# mr_radar_ferret.net
KiCad netlist of a schematic drawn in EAGLE
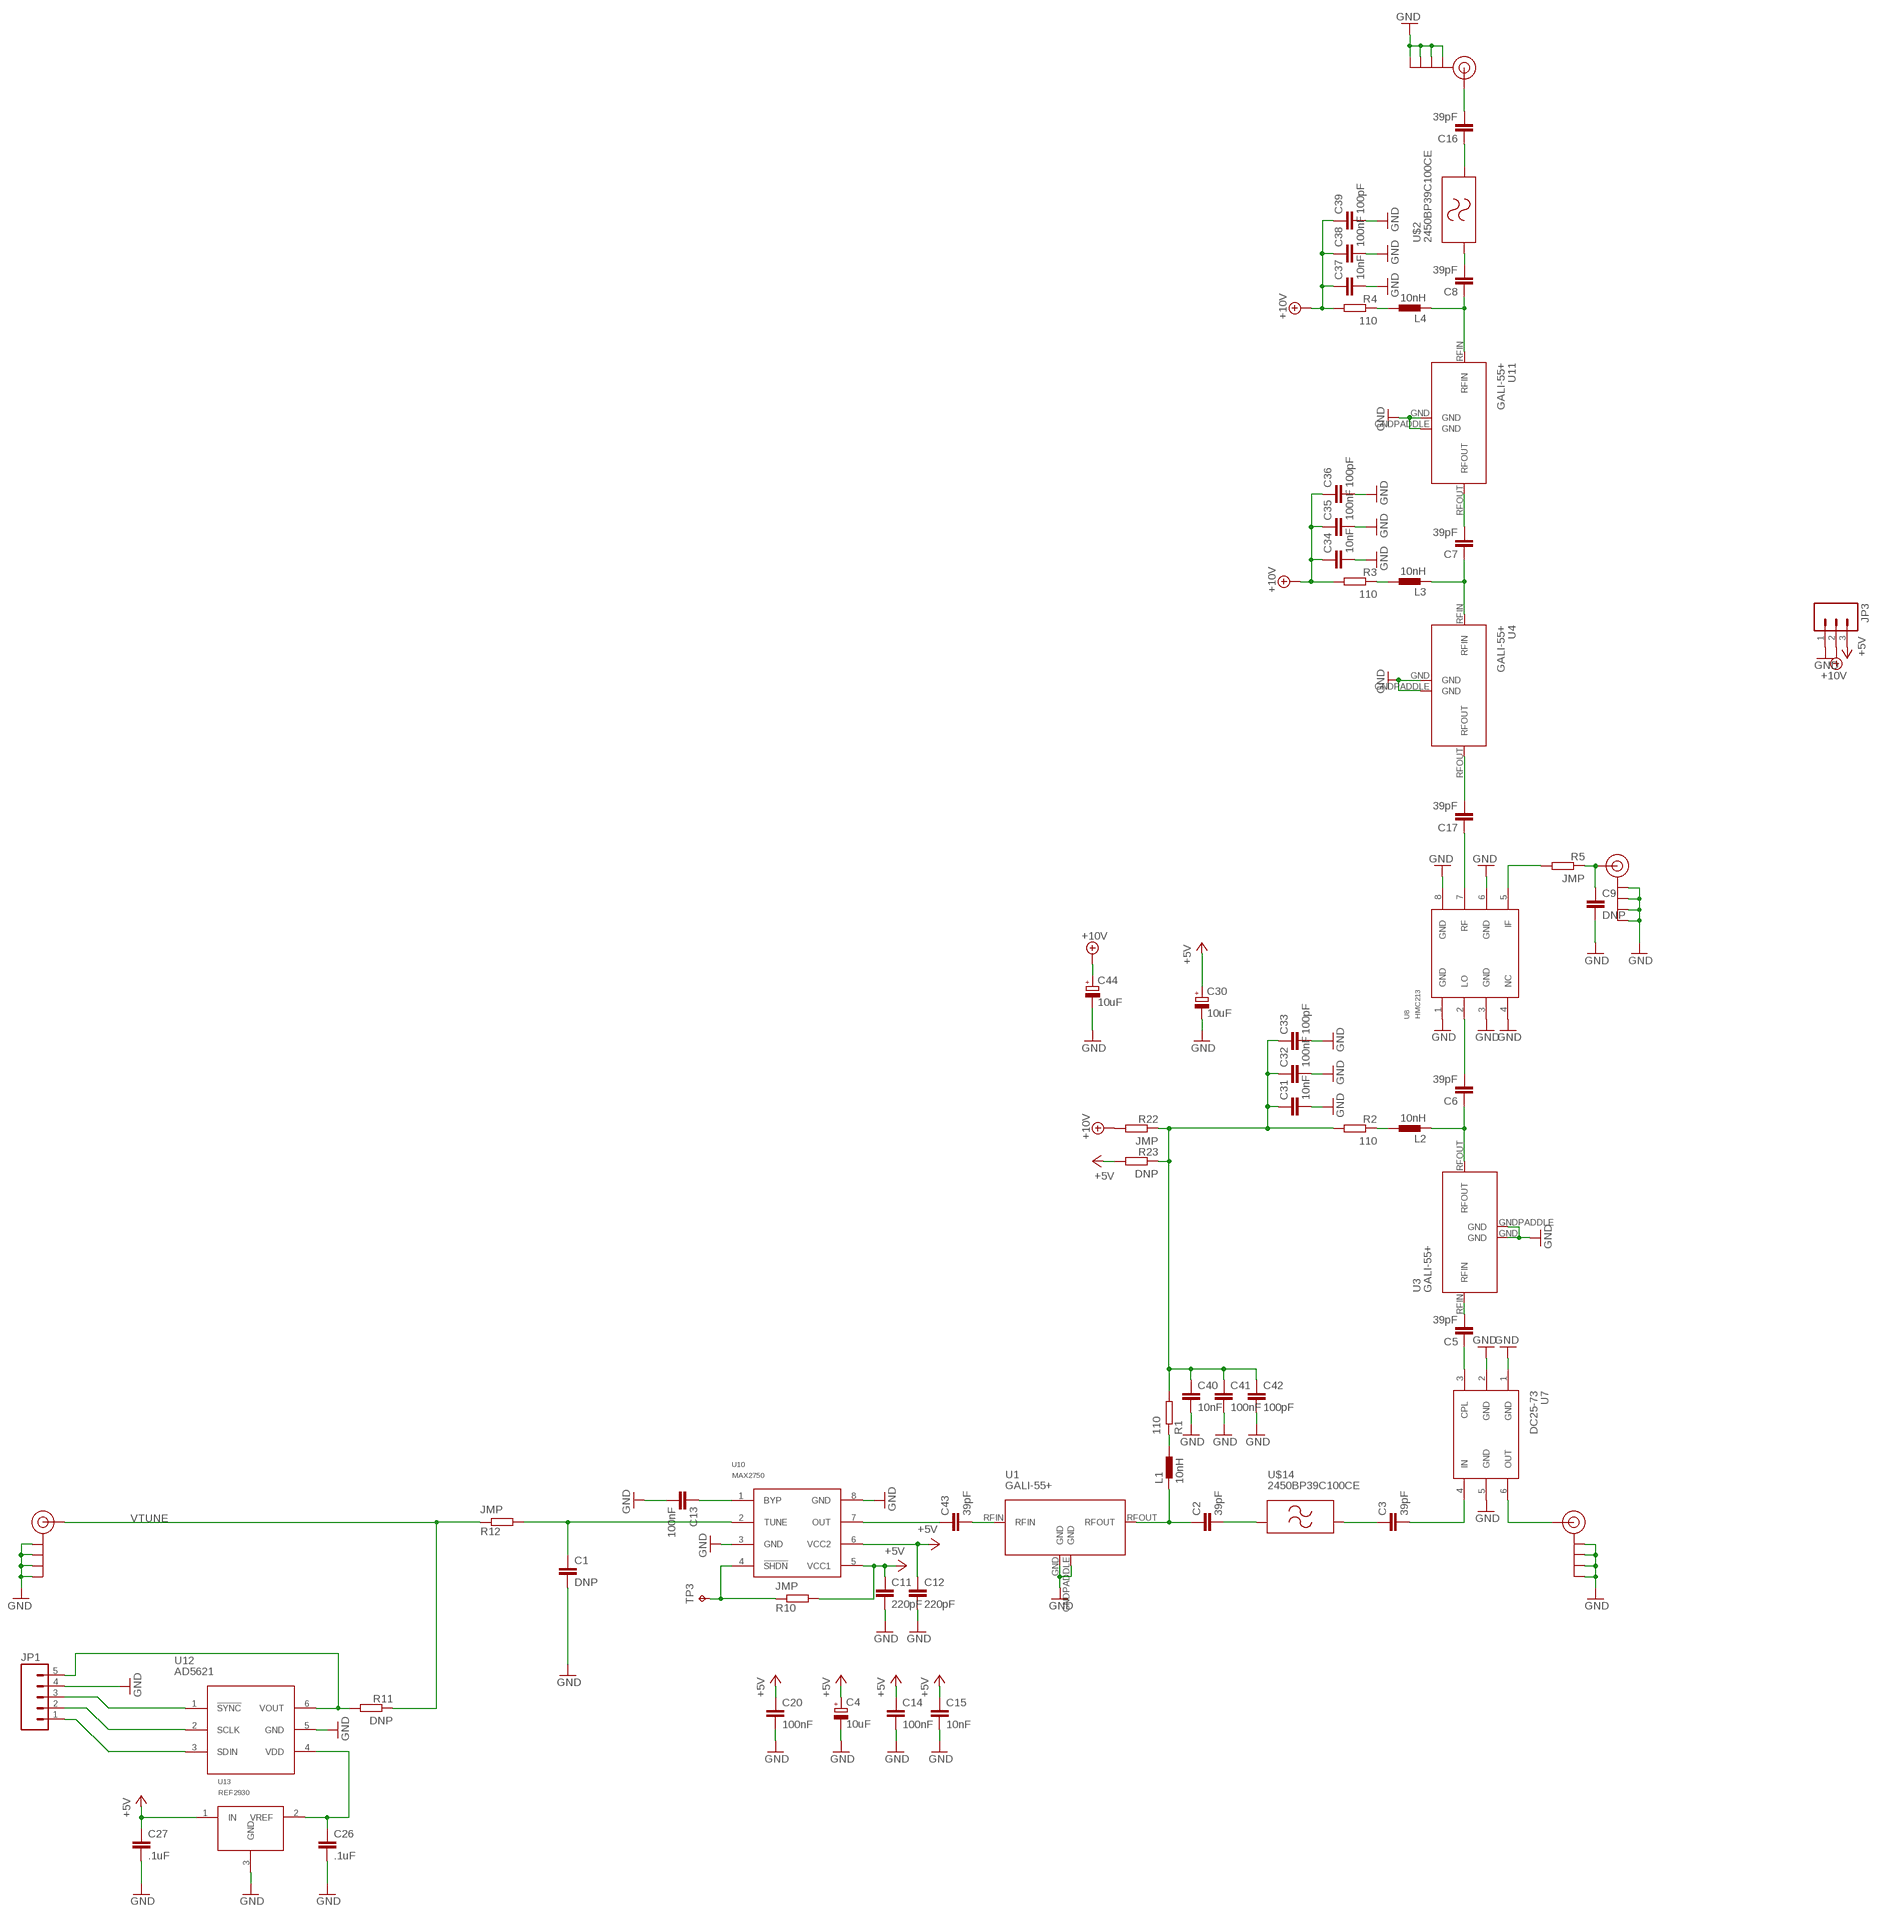
[diagram p0: schematic, sheet 1]

(export (version "E")
  (design (tool "Eeschema 10.0.6"))
  (components
    (comp (ref "C1")
      (value "DNP")
      (footprint "eagle-import:0603-CAP")
      (libsource (lib "eagle-import") (part "CAPACITOR-0603"))
    )
    (comp (ref "C2")
      (value "39pF")
      (footprint "eagle-import:0603-CAP")
      (libsource (lib "eagle-import") (part "CAPACITOR-0603"))
    )
    (comp (ref "C3")
      (value "39pF")
      (footprint "eagle-import:0603-CAP")
      (libsource (lib "eagle-import") (part "CAPACITOR-0603"))
    )
    (comp (ref "C4")
      (value "10uF")
      (footprint "eagle-import:3216_A")
      (libsource (lib "eagle-import") (part "CAPACITOR-POLA"))
    )
    (comp (ref "C5")
      (value "39pF")
      (footprint "eagle-import:0603-CAP")
      (libsource (lib "eagle-import") (part "CAPACITOR-0603"))
    )
    (comp (ref "C6")
      (value "39pF")
      (footprint "eagle-import:0603-CAP")
      (libsource (lib "eagle-import") (part "CAPACITOR-0603"))
    )
    (comp (ref "C7")
      (value "39pF")
      (footprint "eagle-import:0603-CAP")
      (libsource (lib "eagle-import") (part "CAPACITOR-0603"))
    )
    (comp (ref "C8")
      (value "39pF")
      (footprint "eagle-import:0603-CAP")
      (libsource (lib "eagle-import") (part "CAPACITOR-0603"))
    )
    (comp (ref "C9")
      (value "DNP")
      (footprint "eagle-import:0603-CAP")
      (libsource (lib "eagle-import") (part "CAPACITOR-0603"))
    )
    (comp (ref "C11")
      (value "220pF")
      (footprint "eagle-import:0603-CAP")
      (libsource (lib "eagle-import") (part "CAPACITOR-0603"))
    )
    (comp (ref "C12")
      (value "220pF")
      (footprint "eagle-import:0603-CAP")
      (libsource (lib "eagle-import") (part "CAPACITOR-0603"))
    )
    (comp (ref "C13")
      (value "100nF")
      (footprint "eagle-import:0603-CAP")
      (libsource (lib "eagle-import") (part "CAPACITOR-0603"))
    )
    (comp (ref "C14")
      (value "100nF")
      (footprint "eagle-import:0603-CAP")
      (libsource (lib "eagle-import") (part "CAPACITOR-0603"))
    )
    (comp (ref "C15")
      (value "10nF")
      (footprint "eagle-import:0603-CAP")
      (libsource (lib "eagle-import") (part "CAPACITOR-0603"))
    )
    (comp (ref "C16")
      (value "39pF")
      (footprint "eagle-import:0603-CAP")
      (libsource (lib "eagle-import") (part "CAPACITOR-0603"))
    )
    (comp (ref "C17")
      (value "39pF")
      (footprint "eagle-import:0603-CAP")
      (libsource (lib "eagle-import") (part "CAPACITOR-0603"))
    )
    (comp (ref "C20")
      (value "100nF")
      (footprint "eagle-import:0603-CAP")
      (libsource (lib "eagle-import") (part "CAPACITOR-0603"))
    )
    (comp (ref "C26")
      (value ".1uF")
      (footprint "eagle-import:0603-CAP")
      (libsource (lib "eagle-import") (part "CAPACITOR-0603"))
    )
    (comp (ref "C27")
      (value ".1uF")
      (footprint "eagle-import:0603-CAP")
      (libsource (lib "eagle-import") (part "CAPACITOR-0603"))
    )
    (comp (ref "C30")
      (value "10uF")
      (footprint "eagle-import:3216_A")
      (libsource (lib "eagle-import") (part "CAPACITOR-POLA"))
    )
    (comp (ref "C31")
      (value "10nF")
      (footprint "eagle-import:0603-CAP")
      (libsource (lib "eagle-import") (part "CAPACITOR-0603"))
    )
    (comp (ref "C32")
      (value "100nF")
      (footprint "eagle-import:0603-CAP")
      (libsource (lib "eagle-import") (part "CAPACITOR-0603"))
    )
    (comp (ref "C33")
      (value "100pF")
      (footprint "eagle-import:0603-CAP")
      (libsource (lib "eagle-import") (part "CAPACITOR-0603"))
    )
    (comp (ref "C34")
      (value "10nF")
      (footprint "eagle-import:0603-CAP")
      (libsource (lib "eagle-import") (part "CAPACITOR-0603"))
    )
    (comp (ref "C35")
      (value "100nF")
      (footprint "eagle-import:0603-CAP")
      (libsource (lib "eagle-import") (part "CAPACITOR-0603"))
    )
    (comp (ref "C36")
      (value "100pF")
      (footprint "eagle-import:0603-CAP")
      (libsource (lib "eagle-import") (part "CAPACITOR-0603"))
    )
    (comp (ref "C37")
      (value "10nF")
      (footprint "eagle-import:0603-CAP")
      (libsource (lib "eagle-import") (part "CAPACITOR-0603"))
    )
    (comp (ref "C38")
      (value "100nF")
      (footprint "eagle-import:0603-CAP")
      (libsource (lib "eagle-import") (part "CAPACITOR-0603"))
    )
    (comp (ref "C39")
      (value "100pF")
      (footprint "eagle-import:0603-CAP")
      (libsource (lib "eagle-import") (part "CAPACITOR-0603"))
    )
    (comp (ref "C40")
      (value "10nF")
      (footprint "eagle-import:0603-CAP")
      (libsource (lib "eagle-import") (part "CAPACITOR-0603"))
    )
    (comp (ref "C41")
      (value "100nF")
      (footprint "eagle-import:0603-CAP")
      (libsource (lib "eagle-import") (part "CAPACITOR-0603"))
    )
    (comp (ref "C42")
      (value "100pF")
      (footprint "eagle-import:0603-CAP")
      (libsource (lib "eagle-import") (part "CAPACITOR-0603"))
    )
    (comp (ref "C43")
      (value "39pF")
      (footprint "eagle-import:0603-CAP")
      (libsource (lib "eagle-import") (part "CAPACITOR-0603"))
    )
    (comp (ref "C44")
      (value "10uF")
      (footprint "eagle-import:3216_A")
      (libsource (lib "eagle-import") (part "CAPACITOR-POLA"))
    )
    (comp (ref "J$1")
      (value "SMA_EDGE")
      (footprint "eagle-import:SMA-EDGE")
      (libsource (lib "eagle-import") (part "SMA_EDGE"))
    )
    (comp (ref "J$2")
      (value "SMA_EDGE")
      (footprint "eagle-import:SMA-EDGE")
      (libsource (lib "eagle-import") (part "SMA_EDGE"))
    )
    (comp (ref "J$4")
      (value "SMA_EDGE")
      (footprint "eagle-import:SMA-EDGE")
      (libsource (lib "eagle-import") (part "SMA_EDGE"))
    )
    (comp (ref "J$5")
      (value "SMA_EDGE")
      (footprint "eagle-import:SMA-EDGE")
      (libsource (lib "eagle-import") (part "SMA_EDGE"))
    )
    (comp (ref "JP1")
      (value "M05PTH")
      (footprint "eagle-import:1X05")
      (libsource (lib "eagle-import") (part "M05PTH"))
    )
    (comp (ref "JP3")
      (value "M03SCREW")
      (footprint "eagle-import:SCREWTERMINAL-3.5MM-3")
      (libsource (lib "eagle-import") (part "M03SCREW"))
    )
    (comp (ref "L1")
      (value "10nH")
      (footprint "eagle-import:0603-IND")
      (libsource (lib "eagle-import") (part "INDUCTOR-0603"))
    )
    (comp (ref "L2")
      (value "10nH")
      (footprint "eagle-import:0603-IND")
      (libsource (lib "eagle-import") (part "INDUCTOR-0603"))
    )
    (comp (ref "L3")
      (value "10nH")
      (footprint "eagle-import:0603-IND")
      (libsource (lib "eagle-import") (part "INDUCTOR-0603"))
    )
    (comp (ref "L4")
      (value "10nH")
      (footprint "eagle-import:0603-IND")
      (libsource (lib "eagle-import") (part "INDUCTOR-0603"))
    )
    (comp (ref "R1")
      (value "110")
      (footprint "eagle-import:0603-RES")
      (libsource (lib "eagle-import") (part "RESISTOR-0603"))
    )
    (comp (ref "R2")
      (value "110")
      (footprint "eagle-import:0603-RES")
      (libsource (lib "eagle-import") (part "RESISTOR-0603"))
    )
    (comp (ref "R3")
      (value "110")
      (footprint "eagle-import:0603-RES")
      (libsource (lib "eagle-import") (part "RESISTOR-0603"))
    )
    (comp (ref "R4")
      (value "110")
      (footprint "eagle-import:0603-RES")
      (libsource (lib "eagle-import") (part "RESISTOR-0603"))
    )
    (comp (ref "R5")
      (value "JMP")
      (footprint "eagle-import:0603-RES")
      (libsource (lib "eagle-import") (part "RESISTOR-0603"))
    )
    (comp (ref "R10")
      (value "JMP")
      (footprint "eagle-import:0603-RES")
      (libsource (lib "eagle-import") (part "RESISTOR-0603"))
    )
    (comp (ref "R11")
      (value "DNP")
      (footprint "eagle-import:0603-RES")
      (libsource (lib "eagle-import") (part "RESISTOR-0603"))
    )
    (comp (ref "R12")
      (value "JMP")
      (footprint "eagle-import:0603-RES")
      (libsource (lib "eagle-import") (part "RESISTOR-0603"))
    )
    (comp (ref "R22")
      (value "JMP")
      (footprint "eagle-import:0603-RES")
      (libsource (lib "eagle-import") (part "RESISTOR-0603"))
    )
    (comp (ref "R23")
      (value "DNP")
      (footprint "eagle-import:0603-RES")
      (libsource (lib "eagle-import") (part "RESISTOR-0603"))
    )
    (comp (ref "TP3")
      (value "TPTP14SQ")
      (footprint "eagle-import:TP14SQ")
      (libsource (lib "eagle-import") (part "TPTP14SQ"))
    )
    (comp (ref "U$2")
      (value "2450BP39C100CE")
      (footprint "eagle-import:2450BP39C100C")
      (libsource (lib "eagle-import") (part "2450BP39C100CE"))
    )
    (comp (ref "U$14")
      (value "2450BP39C100CE")
      (footprint "eagle-import:2450BP39C100C")
      (libsource (lib "eagle-import") (part "2450BP39C100CE"))
    )
    (comp (ref "U1")
      (value "GALI-55+")
      (footprint "eagle-import:SOT89")
      (libsource (lib "eagle-import") (part "GALI-55+"))
    )
    (comp (ref "U3")
      (value "GALI-55+")
      (footprint "eagle-import:SOT89")
      (libsource (lib "eagle-import") (part "GALI-55+"))
    )
    (comp (ref "U4")
      (value "GALI-55+")
      (footprint "eagle-import:SOT89")
      (libsource (lib "eagle-import") (part "GALI-55+"))
    )
    (comp (ref "U7")
      (value "DC25-73")
      (footprint "eagle-import:SOT23-6")
      (libsource (lib "eagle-import") (part "DC25-73"))
    )
    (comp (ref "U8")
      (value "HMC213")
      (footprint "eagle-import:UMAX8")
      (libsource (lib "eagle-import") (part "HMC213"))
    )
    (comp (ref "U10")
      (value "MAX2750")
      (footprint "eagle-import:UMAX8")
      (libsource (lib "eagle-import") (part "MAX2750"))
    )
    (comp (ref "U11")
      (value "GALI-55+")
      (footprint "eagle-import:SOT89")
      (libsource (lib "eagle-import") (part "GALI-55+"))
    )
    (comp (ref "U12")
      (value "AD5621")
      (footprint "eagle-import:SC70-6L")
      (libsource (lib "eagle-import") (part "AD5621"))
    )
    (comp (ref "U13")
      (value "REF2930")
      (footprint "eagle-import:SOT23-3")
      (libsource (lib "eagle-import") (part "REF2930"))
    )
  )
  (nets
    (net (code "1") (name "+5V") (class "Default")
      (node (ref "C11") (pin "P$1") (pinfunction "1_P$1") (pintype "passive"))
      (node (ref "C12") (pin "P$1") (pinfunction "1_P$1") (pintype "passive"))
      (node (ref "C14") (pin "P$1") (pinfunction "1_P$1") (pintype "passive"))
      (node (ref "C15") (pin "P$1") (pinfunction "1_P$1") (pintype "passive"))
      (node (ref "C20") (pin "P$1") (pinfunction "1_P$1") (pintype "passive"))
      (node (ref "C27") (pin "P$1") (pinfunction "1_P$1") (pintype "passive"))
      (node (ref "C30") (pin "+") (pinfunction "+_+") (pintype "passive"))
      (node (ref "C4") (pin "+") (pinfunction "+_+") (pintype "passive"))
      (node (ref "JP3") (pin "3") (pinfunction "3_3") (pintype "passive"))
      (node (ref "R10") (pin "P$2") (pinfunction "2_P$2") (pintype "passive"))
      (node (ref "R23") (pin "P$2") (pinfunction "2_P$2") (pintype "passive"))
      (node (ref "U10") (pin "5") (pinfunction "VCC1_5") (pintype "bidirectional"))
      (node (ref "U10") (pin "6") (pinfunction "VCC2_6") (pintype "bidirectional"))
      (node (ref "U13") (pin "1") (pinfunction "IN_1") (pintype "input"))
    )
    (net (code "2") (name "+10V") (class "Default")
      (node (ref "C34") (pin "P$1") (pinfunction "1_P$1") (pintype "passive"))
      (node (ref "C35") (pin "P$1") (pinfunction "1_P$1") (pintype "passive"))
      (node (ref "C36") (pin "P$1") (pinfunction "1_P$1") (pintype "passive"))
      (node (ref "C37") (pin "P$1") (pinfunction "1_P$1") (pintype "passive"))
      (node (ref "C38") (pin "P$1") (pinfunction "1_P$1") (pintype "passive"))
      (node (ref "C39") (pin "P$1") (pinfunction "1_P$1") (pintype "passive"))
      (node (ref "C44") (pin "+") (pinfunction "+_+") (pintype "passive"))
      (node (ref "JP3") (pin "2") (pinfunction "2_2") (pintype "passive"))
      (node (ref "R22") (pin "P$2") (pinfunction "2_P$2") (pintype "passive"))
      (node (ref "R3") (pin "P$2") (pinfunction "2_P$2") (pintype "passive"))
      (node (ref "R4") (pin "P$2") (pinfunction "2_P$2") (pintype "passive"))
    )
    (net (code "3") (name "/VTUNE") (class "Default")
      (node (ref "J$4") (pin "SIG") (pinfunction "SIGNAL_SIG") (pintype "bidirectional"))
      (node (ref "R11") (pin "P$1") (pinfunction "1_P$1") (pintype "passive"))
      (node (ref "R12") (pin "P$1") (pinfunction "1_P$1") (pintype "passive"))
    )
    (net (code "4") (name "GND") (class "Default")
      (node (ref "C1") (pin "P$2") (pinfunction "2_P$2") (pintype "passive"))
      (node (ref "C11") (pin "P$2") (pinfunction "2_P$2") (pintype "passive"))
      (node (ref "C12") (pin "P$2") (pinfunction "2_P$2") (pintype "passive"))
      (node (ref "C13") (pin "P$2") (pinfunction "2_P$2") (pintype "passive"))
      (node (ref "C14") (pin "P$2") (pinfunction "2_P$2") (pintype "passive"))
      (node (ref "C15") (pin "P$2") (pinfunction "2_P$2") (pintype "passive"))
      (node (ref "C20") (pin "P$2") (pinfunction "2_P$2") (pintype "passive"))
      (node (ref "C26") (pin "P$2") (pinfunction "2_P$2") (pintype "passive"))
      (node (ref "C27") (pin "P$2") (pinfunction "2_P$2") (pintype "passive"))
      (node (ref "C30") (pin "-") (pinfunction "-_-") (pintype "passive"))
      (node (ref "C31") (pin "P$2") (pinfunction "2_P$2") (pintype "passive"))
      (node (ref "C32") (pin "P$2") (pinfunction "2_P$2") (pintype "passive"))
      (node (ref "C33") (pin "P$2") (pinfunction "2_P$2") (pintype "passive"))
      (node (ref "C34") (pin "P$2") (pinfunction "2_P$2") (pintype "passive"))
      (node (ref "C35") (pin "P$2") (pinfunction "2_P$2") (pintype "passive"))
      (node (ref "C36") (pin "P$2") (pinfunction "2_P$2") (pintype "passive"))
      (node (ref "C37") (pin "P$2") (pinfunction "2_P$2") (pintype "passive"))
      (node (ref "C38") (pin "P$2") (pinfunction "2_P$2") (pintype "passive"))
      (node (ref "C39") (pin "P$2") (pinfunction "2_P$2") (pintype "passive"))
      (node (ref "C4") (pin "-") (pinfunction "-_-") (pintype "passive"))
      (node (ref "C40") (pin "P$2") (pinfunction "2_P$2") (pintype "passive"))
      (node (ref "C41") (pin "P$2") (pinfunction "2_P$2") (pintype "passive"))
      (node (ref "C42") (pin "P$2") (pinfunction "2_P$2") (pintype "passive"))
      (node (ref "C44") (pin "-") (pinfunction "-_-") (pintype "passive"))
      (node (ref "C9") (pin "P$2") (pinfunction "2_P$2") (pintype "passive"))
      (node (ref "J$1") (pin "GND@0") (pinfunction "GND_GND@0") (pintype "bidirectional"))
      (node (ref "J$1") (pin "GND@1") (pinfunction "GND_GND@1") (pintype "bidirectional"))
      (node (ref "J$1") (pin "GND@2") (pinfunction "GND_GND@2") (pintype "bidirectional"))
      (node (ref "J$1") (pin "GND@3") (pinfunction "GND_GND@3") (pintype "bidirectional"))
      (node (ref "J$2") (pin "GND@0") (pinfunction "GND_GND@0") (pintype "bidirectional"))
      (node (ref "J$2") (pin "GND@1") (pinfunction "GND_GND@1") (pintype "bidirectional"))
      (node (ref "J$2") (pin "GND@2") (pinfunction "GND_GND@2") (pintype "bidirectional"))
      (node (ref "J$2") (pin "GND@3") (pinfunction "GND_GND@3") (pintype "bidirectional"))
      (node (ref "J$4") (pin "GND@0") (pinfunction "GND_GND@0") (pintype "bidirectional"))
      (node (ref "J$4") (pin "GND@1") (pinfunction "GND_GND@1") (pintype "bidirectional"))
      (node (ref "J$4") (pin "GND@2") (pinfunction "GND_GND@2") (pintype "bidirectional"))
      (node (ref "J$4") (pin "GND@3") (pinfunction "GND_GND@3") (pintype "bidirectional"))
      (node (ref "J$5") (pin "GND@0") (pinfunction "GND_GND@0") (pintype "bidirectional"))
      (node (ref "J$5") (pin "GND@1") (pinfunction "GND_GND@1") (pintype "bidirectional"))
      (node (ref "J$5") (pin "GND@2") (pinfunction "GND_GND@2") (pintype "bidirectional"))
      (node (ref "J$5") (pin "GND@3") (pinfunction "GND_GND@3") (pintype "bidirectional"))
      (node (ref "JP1") (pin "4") (pinfunction "4_4") (pintype "passive"))
      (node (ref "JP3") (pin "1") (pinfunction "1_1") (pintype "passive"))
      (node (ref "U1") (pin "GND") (pinfunction "GND_GND") (pintype "power_in"))
      (node (ref "U1") (pin "GNDPADDLE") (pinfunction "GND_GNDPADDLE") (pintype "power_in"))
      (node (ref "U10") (pin "3") (pinfunction "GND_3") (pintype "bidirectional"))
      (node (ref "U10") (pin "8") (pinfunction "GND_8") (pintype "bidirectional"))
      (node (ref "U11") (pin "GND") (pinfunction "GND_GND") (pintype "power_in"))
      (node (ref "U11") (pin "GNDPADDLE") (pinfunction "GND_GNDPADDLE") (pintype "power_in"))
      (node (ref "U12") (pin "5") (pinfunction "GND_5") (pintype "bidirectional"))
      (node (ref "U13") (pin "3") (pinfunction "GND_3") (pintype "bidirectional"))
      (node (ref "U3") (pin "GND") (pinfunction "GND_GND") (pintype "power_in"))
      (node (ref "U3") (pin "GNDPADDLE") (pinfunction "GND_GNDPADDLE") (pintype "power_in"))
      (node (ref "U4") (pin "GND") (pinfunction "GND_GND") (pintype "power_in"))
      (node (ref "U4") (pin "GNDPADDLE") (pinfunction "GND_GNDPADDLE") (pintype "power_in"))
      (node (ref "U7") (pin "1") (pinfunction "GND_1") (pintype "bidirectional"))
      (node (ref "U7") (pin "2") (pinfunction "GND_2") (pintype "bidirectional"))
      (node (ref "U7") (pin "5") (pinfunction "GND_5") (pintype "bidirectional"))
      (node (ref "U8") (pin "1") (pinfunction "GND_1") (pintype "bidirectional"))
      (node (ref "U8") (pin "3") (pinfunction "GND_3") (pintype "bidirectional"))
      (node (ref "U8") (pin "4") (pinfunction "NC_4") (pintype "bidirectional"))
      (node (ref "U8") (pin "6") (pinfunction "GND_6") (pintype "bidirectional"))
      (node (ref "U8") (pin "8") (pinfunction "GND_8") (pintype "bidirectional"))
    )
    (net (code "5") (name "Net-(C1-1)") (class "Default")
      (node (ref "C1") (pin "P$1") (pinfunction "1_P$1") (pintype "passive"))
      (node (ref "R12") (pin "P$2") (pinfunction "2_P$2") (pintype "passive"))
      (node (ref "U10") (pin "2") (pinfunction "TUNE_2") (pintype "bidirectional"))
    )
    (net (code "6") (name "Net-(C2-1)") (class "Default")
      (node (ref "C2") (pin "P$1") (pinfunction "1_P$1") (pintype "passive"))
      (node (ref "L1") (pin "P$2") (pinfunction "2_P$2") (pintype "passive"))
      (node (ref "U1") (pin "RFOUT") (pinfunction "RFOUT_RFOUT") (pintype "output"))
    )
    (net (code "7") (name "Net-(C2-2)") (class "Default")
      (node (ref "C2") (pin "P$2") (pinfunction "2_P$2") (pintype "passive"))
      (node (ref "U$14") (pin "P$2") (pinfunction "P$1_P$2") (pintype "passive"))
    )
    (net (code "8") (name "Net-(C3-1)") (class "Default")
      (node (ref "C3") (pin "P$1") (pinfunction "1_P$1") (pintype "passive"))
      (node (ref "U$14") (pin "P$1") (pinfunction "P$2_P$1") (pintype "passive"))
    )
    (net (code "9") (name "Net-(C3-2)") (class "Default")
      (node (ref "C3") (pin "P$2") (pinfunction "2_P$2") (pintype "passive"))
      (node (ref "U7") (pin "4") (pinfunction "IN_4") (pintype "bidirectional"))
    )
    (net (code "10") (name "Net-(C5-1)") (class "Default")
      (node (ref "C5") (pin "P$1") (pinfunction "1_P$1") (pintype "passive"))
      (node (ref "U7") (pin "3") (pinfunction "CPL_3") (pintype "bidirectional"))
    )
    (net (code "11") (name "Net-(C5-2)") (class "Default")
      (node (ref "C5") (pin "P$2") (pinfunction "2_P$2") (pintype "passive"))
      (node (ref "U3") (pin "RFIN") (pinfunction "RFIN_RFIN") (pintype "input"))
    )
    (net (code "12") (name "Net-(C6-1)") (class "Default")
      (node (ref "C6") (pin "P$1") (pinfunction "1_P$1") (pintype "passive"))
      (node (ref "L2") (pin "P$2") (pinfunction "2_P$2") (pintype "passive"))
      (node (ref "U3") (pin "RFOUT") (pinfunction "RFOUT_RFOUT") (pintype "output"))
    )
    (net (code "13") (name "Net-(C6-2)") (class "Default")
      (node (ref "C6") (pin "P$2") (pinfunction "2_P$2") (pintype "passive"))
      (node (ref "U8") (pin "2") (pinfunction "LO_2") (pintype "bidirectional"))
    )
    (net (code "14") (name "Net-(C7-1)") (class "Default")
      (node (ref "C7") (pin "P$1") (pinfunction "1_P$1") (pintype "passive"))
      (node (ref "L3") (pin "P$2") (pinfunction "2_P$2") (pintype "passive"))
      (node (ref "U4") (pin "RFIN") (pinfunction "RFIN_RFIN") (pintype "input"))
    )
    (net (code "15") (name "Net-(C7-2)") (class "Default")
      (node (ref "C7") (pin "P$2") (pinfunction "2_P$2") (pintype "passive"))
      (node (ref "U11") (pin "RFOUT") (pinfunction "RFOUT_RFOUT") (pintype "output"))
    )
    (net (code "16") (name "Net-(C8-1)") (class "Default")
      (node (ref "C8") (pin "P$1") (pinfunction "1_P$1") (pintype "passive"))
      (node (ref "L4") (pin "P$2") (pinfunction "2_P$2") (pintype "passive"))
      (node (ref "U11") (pin "RFIN") (pinfunction "RFIN_RFIN") (pintype "input"))
    )
    (net (code "17") (name "Net-(C8-2)") (class "Default")
      (node (ref "C8") (pin "P$2") (pinfunction "2_P$2") (pintype "passive"))
      (node (ref "U$2") (pin "P$2") (pinfunction "P$1_P$2") (pintype "passive"))
    )
    (net (code "18") (name "Net-(C9-1)") (class "Default")
      (node (ref "C9") (pin "P$1") (pinfunction "1_P$1") (pintype "passive"))
      (node (ref "J$5") (pin "SIG") (pinfunction "SIGNAL_SIG") (pintype "bidirectional"))
      (node (ref "R5") (pin "P$1") (pinfunction "1_P$1") (pintype "passive"))
    )
    (net (code "19") (name "Net-(C13-1)") (class "Default")
      (node (ref "C13") (pin "P$1") (pinfunction "1_P$1") (pintype "passive"))
      (node (ref "U10") (pin "1") (pinfunction "BYP_1") (pintype "bidirectional"))
    )
    (net (code "20") (name "Net-(C16-1)") (class "Default")
      (node (ref "C16") (pin "P$1") (pinfunction "1_P$1") (pintype "passive"))
      (node (ref "U$2") (pin "P$1") (pinfunction "P$2_P$1") (pintype "passive"))
    )
    (net (code "21") (name "Net-(C16-2)") (class "Default")
      (node (ref "C16") (pin "P$2") (pinfunction "2_P$2") (pintype "passive"))
      (node (ref "J$1") (pin "SIG") (pinfunction "SIGNAL_SIG") (pintype "bidirectional"))
    )
    (net (code "22") (name "Net-(C17-1)") (class "Default")
      (node (ref "C17") (pin "P$1") (pinfunction "1_P$1") (pintype "passive"))
      (node (ref "U8") (pin "7") (pinfunction "RF_7") (pintype "bidirectional"))
    )
    (net (code "23") (name "Net-(C17-2)") (class "Default")
      (node (ref "C17") (pin "P$2") (pinfunction "2_P$2") (pintype "passive"))
      (node (ref "U4") (pin "RFOUT") (pinfunction "RFOUT_RFOUT") (pintype "output"))
    )
    (net (code "24") (name "Net-(C26-1)") (class "Default")
      (node (ref "C26") (pin "P$1") (pinfunction "1_P$1") (pintype "passive"))
      (node (ref "U12") (pin "4") (pinfunction "VDD_4") (pintype "bidirectional"))
      (node (ref "U13") (pin "2") (pinfunction "VREF_2") (pintype "bidirectional"))
    )
    (net (code "25") (name "Net-(C31-1)") (class "Default")
      (node (ref "C31") (pin "P$1") (pinfunction "1_P$1") (pintype "passive"))
      (node (ref "C32") (pin "P$1") (pinfunction "1_P$1") (pintype "passive"))
      (node (ref "C33") (pin "P$1") (pinfunction "1_P$1") (pintype "passive"))
      (node (ref "C40") (pin "P$1") (pinfunction "1_P$1") (pintype "passive"))
      (node (ref "C41") (pin "P$1") (pinfunction "1_P$1") (pintype "passive"))
      (node (ref "C42") (pin "P$1") (pinfunction "1_P$1") (pintype "passive"))
      (node (ref "R1") (pin "P$2") (pinfunction "2_P$2") (pintype "passive"))
      (node (ref "R2") (pin "P$2") (pinfunction "2_P$2") (pintype "passive"))
      (node (ref "R22") (pin "P$1") (pinfunction "1_P$1") (pintype "passive"))
      (node (ref "R23") (pin "P$1") (pinfunction "1_P$1") (pintype "passive"))
    )
    (net (code "26") (name "Net-(C43-1)") (class "Default")
      (node (ref "C43") (pin "P$1") (pinfunction "1_P$1") (pintype "passive"))
      (node (ref "U10") (pin "7") (pinfunction "OUT_7") (pintype "bidirectional"))
    )
    (net (code "27") (name "Net-(C43-2)") (class "Default")
      (node (ref "C43") (pin "P$2") (pinfunction "2_P$2") (pintype "passive"))
      (node (ref "U1") (pin "RFIN") (pinfunction "RFIN_RFIN") (pintype "input"))
    )
    (net (code "28") (name "Net-(J$2-SIGNAL)") (class "Default")
      (node (ref "J$2") (pin "SIG") (pinfunction "SIGNAL_SIG") (pintype "bidirectional"))
      (node (ref "U7") (pin "6") (pinfunction "OUT_6") (pintype "bidirectional"))
    )
    (net (code "29") (name "Net-(L1-1)") (class "Default")
      (node (ref "L1") (pin "P$1") (pinfunction "1_P$1") (pintype "passive"))
      (node (ref "R1") (pin "P$1") (pinfunction "1_P$1") (pintype "passive"))
    )
    (net (code "30") (name "Net-(L2-1)") (class "Default")
      (node (ref "L2") (pin "P$1") (pinfunction "1_P$1") (pintype "passive"))
      (node (ref "R2") (pin "P$1") (pinfunction "1_P$1") (pintype "passive"))
    )
    (net (code "31") (name "Net-(L3-1)") (class "Default")
      (node (ref "L3") (pin "P$1") (pinfunction "1_P$1") (pintype "passive"))
      (node (ref "R3") (pin "P$1") (pinfunction "1_P$1") (pintype "passive"))
    )
    (net (code "32") (name "Net-(L4-1)") (class "Default")
      (node (ref "L4") (pin "P$1") (pinfunction "1_P$1") (pintype "passive"))
      (node (ref "R4") (pin "P$1") (pinfunction "1_P$1") (pintype "passive"))
    )
    (net (code "33") (name "Net-(R5-2)") (class "Default")
      (node (ref "R5") (pin "P$2") (pinfunction "2_P$2") (pintype "passive"))
      (node (ref "U8") (pin "5") (pinfunction "IF_5") (pintype "bidirectional"))
    )
    (net (code "34") (name "Net-(R10-1)") (class "Default")
      (node (ref "R10") (pin "P$1") (pinfunction "1_P$1") (pintype "passive"))
      (node (ref "TP3") (pin "TP") (pinfunction "TP_TP") (pintype "input"))
      (node (ref "U10") (pin "4") (pinfunction "~{SHDN}_4") (pintype "bidirectional"))
    )
    (net (code "35") (name "Net-(R11-2)") (class "Default")
      (node (ref "JP1") (pin "5") (pinfunction "5_5") (pintype "passive"))
      (node (ref "R11") (pin "P$2") (pinfunction "2_P$2") (pintype "passive"))
      (node (ref "U12") (pin "6") (pinfunction "VOUT_6") (pintype "bidirectional"))
    )
    (net (code "36") (name "Net-(U12-SCLK)") (class "Default")
      (node (ref "JP1") (pin "2") (pinfunction "2_2") (pintype "passive"))
      (node (ref "U12") (pin "2") (pinfunction "SCLK_2") (pintype "bidirectional"))
    )
    (net (code "37") (name "Net-(U12-SDIN)") (class "Default")
      (node (ref "JP1") (pin "1") (pinfunction "1_1") (pintype "passive"))
      (node (ref "U12") (pin "3") (pinfunction "SDIN_3") (pintype "bidirectional"))
    )
    (net (code "38") (name "Net-(U12-~{SYNC})") (class "Default")
      (node (ref "JP1") (pin "3") (pinfunction "3_3") (pintype "passive"))
      (node (ref "U12") (pin "1") (pinfunction "~{SYNC}_1") (pintype "bidirectional"))
    )
  )
)
